# v0_3.net
KiCad netlist of a schematic drawn in EAGLE
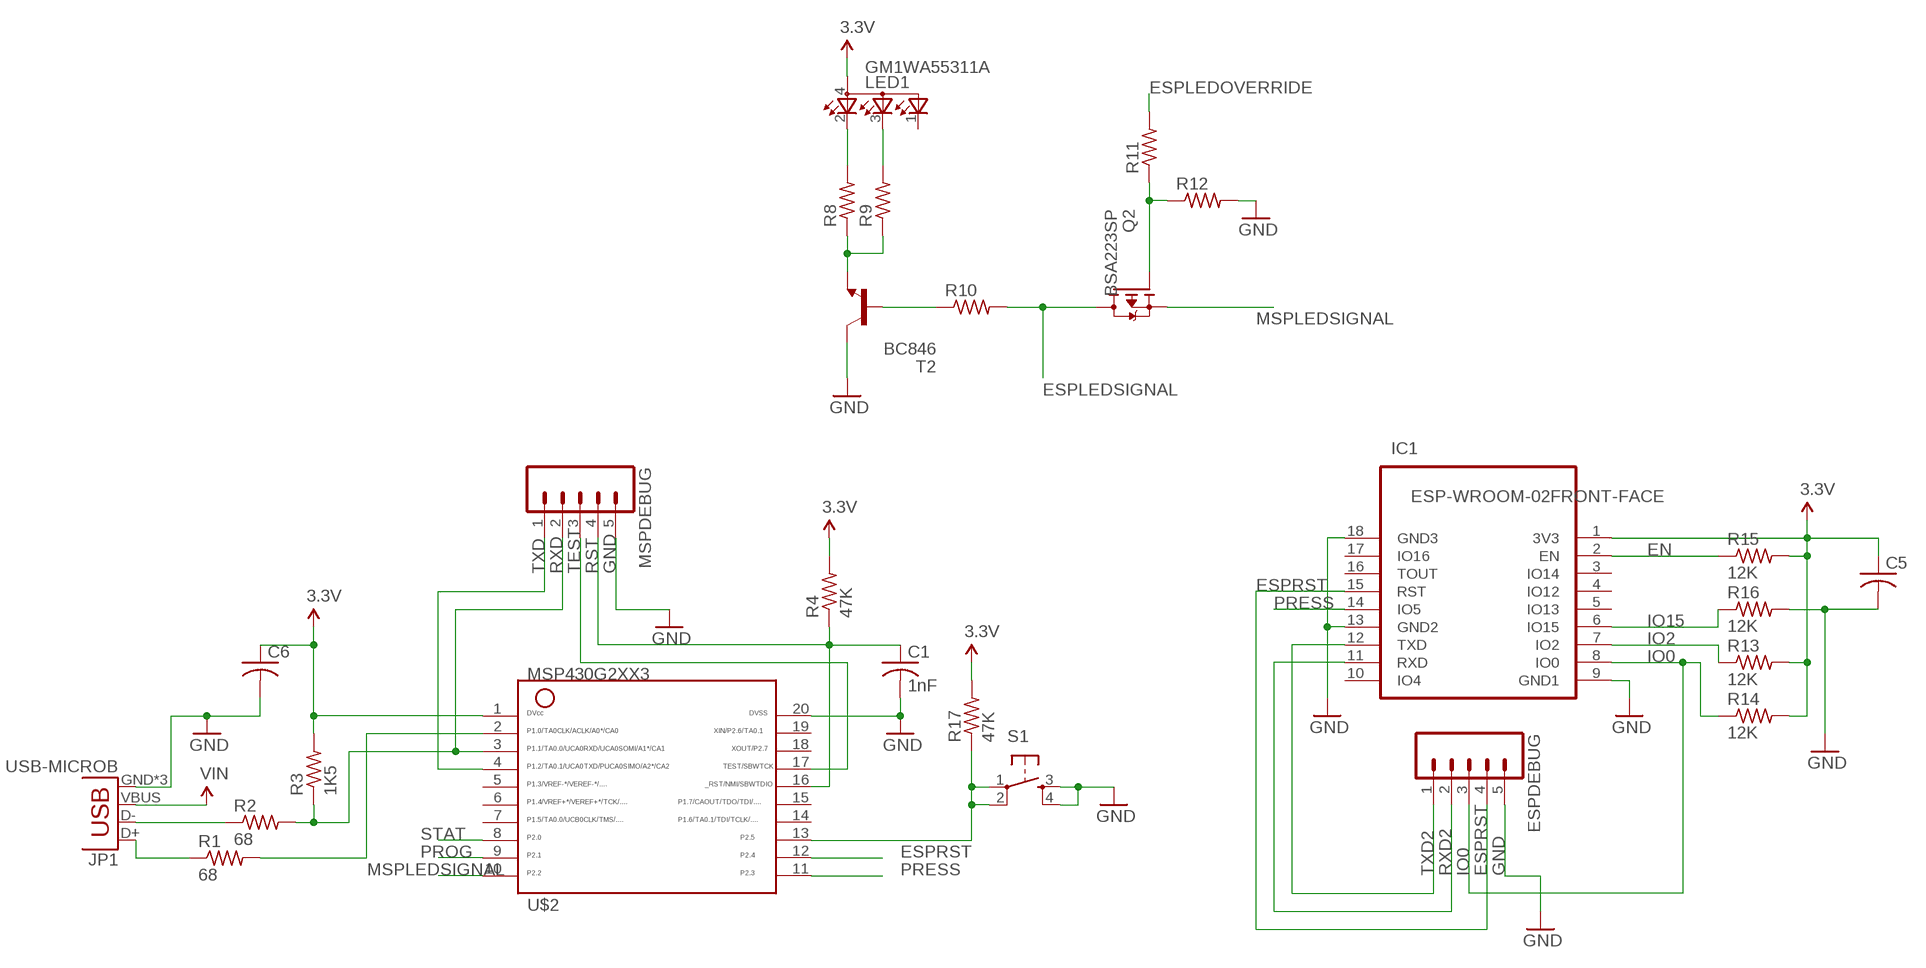
[diagram p0: schematic, sheet 1]
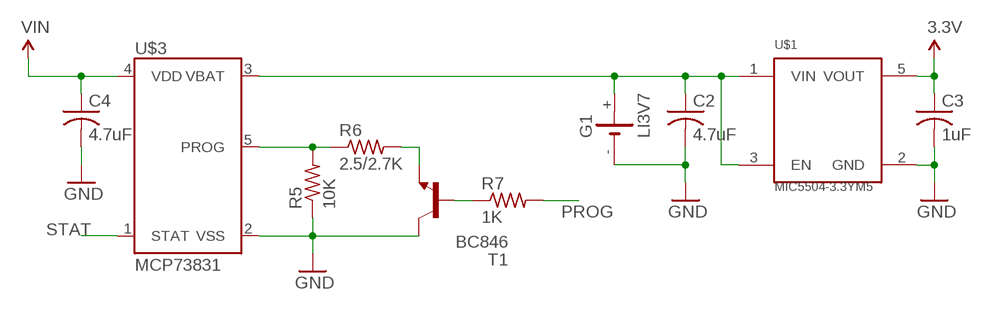
[diagram p1: schematic, sheet 2]

(export (version "E")
  (design (tool "Eeschema 10.0.6"))
  (components
    (comp (ref "C2")
      (value "4.7uF")
      (footprint "eagle-import:C0603K")
      (libsource (lib "eagle-import") (part "C-USC0603K"))
    )
    (comp (ref "C3")
      (value "1uF")
      (footprint "eagle-import:C0603K")
      (libsource (lib "eagle-import") (part "C-USC0603K"))
    )
    (comp (ref "C4")
      (value "4.7uF")
      (footprint "eagle-import:C0603K")
      (libsource (lib "eagle-import") (part "C-USC0603K"))
    )
    (comp (ref "G1")
      (value "LI3V7")
      (footprint "eagle-import:LI3V7")
      (libsource (lib "eagle-import") (part "LI3V7"))
    )
    (comp (ref "R5")
      (value "10K")
      (footprint "eagle-import:R0603")
      (libsource (lib "eagle-import") (part "R-US_R0603"))
    )
    (comp (ref "R6")
      (value "2.5/2.7K")
      (footprint "eagle-import:R0603")
      (libsource (lib "eagle-import") (part "R-US_R0603"))
    )
    (comp (ref "R7")
      (value "1K")
      (footprint "eagle-import:R0603")
      (libsource (lib "eagle-import") (part "R-US_R0603"))
    )
    (comp (ref "T1")
      (value "BC846")
      (footprint "eagle-import:SOT23")
      (libsource (lib "eagle-import") (part "BC846"))
    )
    (comp (ref "U$1")
      (value "MIC5504-3.3YM5")
      (footprint "eagle-import:SOT23-5")
      (libsource (lib "eagle-import") (part "MIC5504-3.3YM5"))
    )
    (comp (ref "U$3")
      (value "MCP73831")
      (footprint "eagle-import:SOT23-5")
      (libsource (lib "eagle-import") (part "MCP73831"))
    )
    (comp (ref "C1")
      (value "1nF")
      (footprint "eagle-import:C0603K")
      (libsource (lib "eagle-import") (part "C-USC0603K"))
    )
    (comp (ref "C5")
      (value "C-USC0603K")
      (footprint "eagle-import:C0603K")
      (libsource (lib "eagle-import") (part "C-USC0603K"))
    )
    (comp (ref "C6")
      (value "C-USC0603K")
      (footprint "eagle-import:C0603K")
      (libsource (lib "eagle-import") (part "C-USC0603K"))
    )
    (comp (ref "ESPDEBUG")
      (value "M05LOCK")
      (footprint "eagle-import:1X05_LOCK")
      (libsource (lib "eagle-import") (part "M05LOCK"))
    )
    (comp (ref "IC1")
      (value "ESP-WROOM-02FRONT-FACE")
      (footprint "eagle-import:FRONT-FACE")
      (libsource (lib "eagle-import") (part "ESP-WROOM-02FRONT-FACE"))
    )
    (comp (ref "JP1")
      (value "USB-MICROB")
      (footprint "eagle-import:USB-MICROB")
      (libsource (lib "eagle-import") (part "USB-MICROB"))
    )
    (comp (ref "LED1")
      (value "GM1WA55311A")
      (footprint "eagle-import:GM1WA55311A")
      (libsource (lib "eagle-import") (part "GM1WA55311A"))
    )
    (comp (ref "MSPDEBUG")
      (value "M05LOCK")
      (footprint "eagle-import:1X05_LOCK")
      (libsource (lib "eagle-import") (part "M05LOCK"))
    )
    (comp (ref "Q2")
      (value "BSA223SP")
      (footprint "eagle-import:SC75_INFINEON")
      (libsource (lib "eagle-import") (part "BSA223SP"))
    )
    (comp (ref "R1")
      (value "68")
      (footprint "eagle-import:R0603")
      (libsource (lib "eagle-import") (part "R-US_R0603"))
    )
    (comp (ref "R2")
      (value "68")
      (footprint "eagle-import:R0603")
      (libsource (lib "eagle-import") (part "R-US_R0603"))
    )
    (comp (ref "R3")
      (value "1K5")
      (footprint "eagle-import:R0603")
      (libsource (lib "eagle-import") (part "R-US_R0603"))
    )
    (comp (ref "R4")
      (value "47K")
      (footprint "eagle-import:R0603")
      (libsource (lib "eagle-import") (part "R-US_R0603"))
    )
    (comp (ref "R8")
      (value "R-US_R0603")
      (footprint "eagle-import:R0603")
      (libsource (lib "eagle-import") (part "R-US_R0603"))
    )
    (comp (ref "R9")
      (value "R-US_R0603")
      (footprint "eagle-import:R0603")
      (libsource (lib "eagle-import") (part "R-US_R0603"))
    )
    (comp (ref "R10")
      (value "R-US_R0603")
      (footprint "eagle-import:R0603")
      (libsource (lib "eagle-import") (part "R-US_R0603"))
    )
    (comp (ref "R11")
      (value "R-US_R0603")
      (footprint "eagle-import:R0603")
      (libsource (lib "eagle-import") (part "R-US_R0603"))
    )
    (comp (ref "R12")
      (value "R-US_R0603")
      (footprint "eagle-import:R0603")
      (libsource (lib "eagle-import") (part "R-US_R0603"))
    )
    (comp (ref "R13")
      (value "12K")
      (footprint "eagle-import:R0603")
      (libsource (lib "eagle-import") (part "R-US_R0603"))
    )
    (comp (ref "R14")
      (value "12K")
      (footprint "eagle-import:R0603")
      (libsource (lib "eagle-import") (part "R-US_R0603"))
    )
    (comp (ref "R15")
      (value "12K")
      (footprint "eagle-import:R0603")
      (libsource (lib "eagle-import") (part "R-US_R0603"))
    )
    (comp (ref "R16")
      (value "12K")
      (footprint "eagle-import:R0603")
      (libsource (lib "eagle-import") (part "R-US_R0603"))
    )
    (comp (ref "R17")
      (value "47K")
      (footprint "eagle-import:R0603")
      (libsource (lib "eagle-import") (part "R-US_R0603"))
    )
    (comp (ref "S1")
      (value "TAC_SWITCHPTH")
      (footprint "eagle-import:TACTILE-PTH")
      (libsource (lib "eagle-import") (part "TAC_SWITCHPTH"))
    )
    (comp (ref "T2")
      (value "BC846")
      (footprint "eagle-import:SOT23")
      (libsource (lib "eagle-import") (part "BC846"))
    )
    (comp (ref "U$2")
      (value "G2XX3---PW20")
      (footprint "eagle-import:PW20")
      (libsource (lib "eagle-import") (part "G2XX3---PW20"))
    )
  )
  (nets
    (net (code "1") (name "3.3V") (class "Default")
      (node (ref "C3") (pin "1") (pinfunction "1_1") (pintype "passive"))
      (node (ref "C5") (pin "1") (pinfunction "1_1") (pintype "passive"))
      (node (ref "C6") (pin "1") (pinfunction "1_1") (pintype "passive"))
      (node (ref "IC1") (pin "1") (pinfunction "3V3_1") (pintype "power_in"))
      (node (ref "LED1") (pin "4") (pinfunction "A_4") (pintype "passive"))
      (node (ref "R13") (pin "2") (pinfunction "2_2") (pintype "passive"))
      (node (ref "R14") (pin "2") (pinfunction "2_2") (pintype "passive"))
      (node (ref "R15") (pin "2") (pinfunction "2_2") (pintype "passive"))
      (node (ref "R17") (pin "2") (pinfunction "2_2") (pintype "passive"))
      (node (ref "R3") (pin "2") (pinfunction "2_2") (pintype "passive"))
      (node (ref "R4") (pin "2") (pinfunction "2_2") (pintype "passive"))
      (node (ref "U$1") (pin "5") (pinfunction "VOUT_5") (pintype "bidirectional"))
      (node (ref "U$2") (pin "1") (pinfunction "1_1") (pintype "bidirectional"))
    )
    (net (code "2") (name "EN") (class "Default")
      (node (ref "IC1") (pin "2") (pinfunction "EN_2") (pintype "bidirectional"))
      (node (ref "R15") (pin "1") (pinfunction "1_1") (pintype "passive"))
    )
    (net (code "3") (name "ESPLEDOVERRIDE") (class "Default")
      (node (ref "R11") (pin "2") (pinfunction "2_2") (pintype "passive"))
    )
    (net (code "4") (name "ESPLEDSIGNAL") (class "Default")
      (node (ref "Q2") (pin "2") (pinfunction "D_2") (pintype "passive"))
      (node (ref "R10") (pin "2") (pinfunction "2_2") (pintype "passive"))
    )
    (net (code "5") (name "ESPRST") (class "Default")
      (node (ref "ESPDEBUG") (pin "4") (pinfunction "4_4") (pintype "passive"))
      (node (ref "IC1") (pin "15") (pinfunction "RST_15") (pintype "bidirectional"))
      (node (ref "U$2") (pin "12") (pinfunction "12_12") (pintype "bidirectional"))
    )
    (net (code "6") (name "GND") (class "Default")
      (node (ref "C1") (pin "2") (pinfunction "2_2") (pintype "passive"))
      (node (ref "C2") (pin "2") (pinfunction "2_2") (pintype "passive"))
      (node (ref "C3") (pin "2") (pinfunction "2_2") (pintype "passive"))
      (node (ref "C4") (pin "2") (pinfunction "2_2") (pintype "passive"))
      (node (ref "C5") (pin "2") (pinfunction "2_2") (pintype "passive"))
      (node (ref "C6") (pin "2") (pinfunction "2_2") (pintype "passive"))
      (node (ref "ESPDEBUG") (pin "5") (pinfunction "5_5") (pintype "passive"))
      (node (ref "G1") (pin "-") (pinfunction "-_-") (pintype "passive"))
      (node (ref "IC1") (pin "13") (pinfunction "GND2_13") (pintype "power_in"))
      (node (ref "IC1") (pin "18") (pinfunction "GND3_18") (pintype "power_in"))
      (node (ref "IC1") (pin "9") (pinfunction "GND1_9") (pintype "power_in"))
      (node (ref "JP1") (pin "GND") (pinfunction "GND_GND") (pintype "bidirectional"))
      (node (ref "JP1") (pin "MT1") (pinfunction "GND_MT1") (pintype "bidirectional"))
      (node (ref "JP1") (pin "MT2") (pinfunction "GND_MT2") (pintype "bidirectional"))
      (node (ref "MSPDEBUG") (pin "5") (pinfunction "5_5") (pintype "passive"))
      (node (ref "R12") (pin "2") (pinfunction "2_2") (pintype "passive"))
      (node (ref "R16") (pin "2") (pinfunction "2_2") (pintype "passive"))
      (node (ref "R5") (pin "1") (pinfunction "1_1") (pintype "passive"))
      (node (ref "S1") (pin "3") (pinfunction "3_3") (pintype "passive"))
      (node (ref "S1") (pin "4") (pinfunction "4_4") (pintype "passive"))
      (node (ref "T1") (pin "3") (pinfunction "C_3") (pintype "passive"))
      (node (ref "T2") (pin "3") (pinfunction "C_3") (pintype "passive"))
      (node (ref "U$1") (pin "2") (pinfunction "GND_2") (pintype "bidirectional"))
      (node (ref "U$2") (pin "20") (pinfunction "20_20") (pintype "bidirectional"))
      (node (ref "U$3") (pin "2") (pinfunction "VSS_2") (pintype "power_in"))
    )
    (net (code "7") (name "IO0") (class "Default")
      (node (ref "ESPDEBUG") (pin "3") (pinfunction "3_3") (pintype "passive"))
      (node (ref "IC1") (pin "8") (pinfunction "IO0_8") (pintype "bidirectional"))
      (node (ref "R14") (pin "1") (pinfunction "1_1") (pintype "passive"))
    )
    (net (code "8") (name "IO2") (class "Default")
      (node (ref "IC1") (pin "7") (pinfunction "IO2_7") (pintype "bidirectional"))
      (node (ref "R13") (pin "1") (pinfunction "1_1") (pintype "passive"))
    )
    (net (code "9") (name "IO15") (class "Default")
      (node (ref "IC1") (pin "6") (pinfunction "IO15_6") (pintype "bidirectional"))
      (node (ref "R16") (pin "1") (pinfunction "1_1") (pintype "passive"))
    )
    (net (code "10") (name "MSPLEDSIGNAL") (class "Default")
      (node (ref "Q2") (pin "3") (pinfunction "S_3") (pintype "passive"))
      (node (ref "U$2") (pin "10") (pinfunction "10_10") (pintype "bidirectional"))
    )
    (net (code "11") (name "Net-(JP1-PadD+)") (class "Default")
      (node (ref "JP1") (pin "D+") (pinfunction "D+_D+") (pintype "bidirectional"))
      (node (ref "R1") (pin "1") (pinfunction "1_1") (pintype "passive"))
    )
    (net (code "12") (name "Net-(JP1-PadD-)") (class "Default")
      (node (ref "JP1") (pin "D-") (pinfunction "D-_D-") (pintype "bidirectional"))
      (node (ref "R2") (pin "1") (pinfunction "1_1") (pintype "passive"))
    )
    (net (code "13") (name "Net-(LED1-CBLUE)") (class "Default")
      (node (ref "LED1") (pin "3") (pinfunction "CBLUE_3") (pintype "passive"))
      (node (ref "R9") (pin "2") (pinfunction "2_2") (pintype "passive"))
    )
    (net (code "14") (name "Net-(LED1-CRED)") (class "Default")
      (node (ref "LED1") (pin "2") (pinfunction "CRED_2") (pintype "passive"))
      (node (ref "R8") (pin "2") (pinfunction "2_2") (pintype "passive"))
    )
    (net (code "15") (name "Net-(Q2-G)") (class "Default")
      (node (ref "Q2") (pin "1") (pinfunction "G_1") (pintype "passive"))
      (node (ref "R11") (pin "1") (pinfunction "1_1") (pintype "passive"))
      (node (ref "R12") (pin "1") (pinfunction "1_1") (pintype "passive"))
    )
    (net (code "16") (name "Net-(R1-Pad2)") (class "Default")
      (node (ref "R1") (pin "2") (pinfunction "2_2") (pintype "passive"))
      (node (ref "U$2") (pin "2") (pinfunction "2_2") (pintype "bidirectional"))
    )
    (net (code "17") (name "Net-(R17-Pad1)") (class "Default")
      (node (ref "R17") (pin "1") (pinfunction "1_1") (pintype "passive"))
      (node (ref "S1") (pin "1") (pinfunction "1_1") (pintype "passive"))
      (node (ref "S1") (pin "2") (pinfunction "2_2") (pintype "passive"))
      (node (ref "U$2") (pin "13") (pinfunction "13_13") (pintype "bidirectional"))
    )
    (net (code "18") (name "Net-(T1-B)") (class "Default")
      (node (ref "R7") (pin "1") (pinfunction "1_1") (pintype "passive"))
      (node (ref "T1") (pin "1") (pinfunction "B_1") (pintype "passive"))
    )
    (net (code "19") (name "Net-(T1-E)") (class "Default")
      (node (ref "R6") (pin "2") (pinfunction "2_2") (pintype "passive"))
      (node (ref "T1") (pin "2") (pinfunction "E_2") (pintype "passive"))
    )
    (net (code "20") (name "Net-(T2-B)") (class "Default")
      (node (ref "R10") (pin "1") (pinfunction "1_1") (pintype "passive"))
      (node (ref "T2") (pin "1") (pinfunction "B_1") (pintype "passive"))
    )
    (net (code "21") (name "Net-(T2-E)") (class "Default")
      (node (ref "R8") (pin "1") (pinfunction "1_1") (pintype "passive"))
      (node (ref "R9") (pin "1") (pinfunction "1_1") (pintype "passive"))
      (node (ref "T2") (pin "2") (pinfunction "E_2") (pintype "passive"))
    )
    (net (code "22") (name "Net-(U$1-EN)") (class "Default")
      (node (ref "C2") (pin "1") (pinfunction "1_1") (pintype "passive"))
      (node (ref "G1") (pin "+") (pinfunction "+_+") (pintype "passive"))
      (node (ref "U$1") (pin "1") (pinfunction "VIN_1") (pintype "bidirectional"))
      (node (ref "U$1") (pin "3") (pinfunction "EN_3") (pintype "bidirectional"))
      (node (ref "U$3") (pin "3") (pinfunction "VBAT_3") (pintype "power_in"))
    )
    (net (code "23") (name "Net-(U$3-PROG)") (class "Default")
      (node (ref "R5") (pin "2") (pinfunction "2_2") (pintype "passive"))
      (node (ref "R6") (pin "1") (pinfunction "1_1") (pintype "passive"))
      (node (ref "U$3") (pin "5") (pinfunction "PROG_5") (pintype "input"))
    )
    (net (code "24") (name "PRESS") (class "Default")
      (node (ref "IC1") (pin "14") (pinfunction "IO5_14") (pintype "open_collector"))
      (node (ref "U$2") (pin "11") (pinfunction "11_11") (pintype "bidirectional"))
    )
    (net (code "25") (name "PROG") (class "Default")
      (node (ref "R7") (pin "2") (pinfunction "2_2") (pintype "passive"))
      (node (ref "U$2") (pin "9") (pinfunction "9_9") (pintype "bidirectional"))
    )
    (net (code "26") (name "RST") (class "Default")
      (node (ref "C1") (pin "1") (pinfunction "1_1") (pintype "passive"))
      (node (ref "MSPDEBUG") (pin "4") (pinfunction "4_4") (pintype "passive"))
      (node (ref "R4") (pin "1") (pinfunction "1_1") (pintype "passive"))
      (node (ref "U$2") (pin "16") (pinfunction "16_16") (pintype "bidirectional"))
    )
    (net (code "27") (name "RXD") (class "Default")
      (node (ref "MSPDEBUG") (pin "2") (pinfunction "2_2") (pintype "passive"))
      (node (ref "R2") (pin "2") (pinfunction "2_2") (pintype "passive"))
      (node (ref "R3") (pin "1") (pinfunction "1_1") (pintype "passive"))
      (node (ref "U$2") (pin "3") (pinfunction "3_3") (pintype "bidirectional"))
    )
    (net (code "28") (name "RXD2") (class "Default")
      (node (ref "ESPDEBUG") (pin "2") (pinfunction "2_2") (pintype "passive"))
      (node (ref "IC1") (pin "11") (pinfunction "RXD_11") (pintype "bidirectional"))
    )
    (net (code "29") (name "STAT") (class "Default")
      (node (ref "U$2") (pin "8") (pinfunction "8_8") (pintype "bidirectional"))
      (node (ref "U$3") (pin "1") (pinfunction "STAT_1") (pintype "output"))
    )
    (net (code "30") (name "TEST") (class "Default")
      (node (ref "MSPDEBUG") (pin "3") (pinfunction "3_3") (pintype "passive"))
      (node (ref "U$2") (pin "17") (pinfunction "17_17") (pintype "bidirectional"))
    )
    (net (code "31") (name "TXD") (class "Default")
      (node (ref "MSPDEBUG") (pin "1") (pinfunction "1_1") (pintype "passive"))
      (node (ref "U$2") (pin "4") (pinfunction "4_4") (pintype "bidirectional"))
    )
    (net (code "32") (name "TXD2") (class "Default")
      (node (ref "ESPDEBUG") (pin "1") (pinfunction "1_1") (pintype "passive"))
      (node (ref "IC1") (pin "12") (pinfunction "TXD_12") (pintype "bidirectional"))
    )
    (net (code "33") (name "VIN") (class "Default")
      (node (ref "C4") (pin "1") (pinfunction "1_1") (pintype "passive"))
      (node (ref "JP1") (pin "VBUS") (pinfunction "VBUS_VBUS") (pintype "bidirectional"))
      (node (ref "U$3") (pin "4") (pinfunction "VDD_4") (pintype "power_in"))
    )
    (net (code "34") (name "unconnected-(IC1-IO4-Pad10)") (class "Default")
      (node (ref "IC1") (pin "10") (pinfunction "IO4_10") (pintype "bidirectional"))
    )
    (net (code "35") (name "unconnected-(IC1-IO12-Pad4)") (class "Default")
      (node (ref "IC1") (pin "4") (pinfunction "IO12_4") (pintype "bidirectional"))
    )
    (net (code "36") (name "unconnected-(IC1-IO13-Pad5)") (class "Default")
      (node (ref "IC1") (pin "5") (pinfunction "IO13_5") (pintype "bidirectional"))
    )
    (net (code "37") (name "unconnected-(IC1-IO14-Pad3)") (class "Default")
      (node (ref "IC1") (pin "3") (pinfunction "IO14_3") (pintype "bidirectional"))
    )
    (net (code "38") (name "unconnected-(IC1-IO16-Pad17)") (class "Default")
      (node (ref "IC1") (pin "17") (pinfunction "IO16_17") (pintype "bidirectional"))
    )
    (net (code "39") (name "unconnected-(IC1-TOUT-Pad16)") (class "Default")
      (node (ref "IC1") (pin "16") (pinfunction "TOUT_16") (pintype "bidirectional"))
    )
    (net (code "40") (name "unconnected-(LED1-CGREEN-Pad1)") (class "Default")
      (node (ref "LED1") (pin "1") (pinfunction "CGREEN_1") (pintype "passive"))
    )
    (net (code "41") (name "unconnected-(U$2-Pad5)") (class "Default")
      (node (ref "U$2") (pin "5") (pinfunction "5_5") (pintype "bidirectional"))
    )
    (net (code "42") (name "unconnected-(U$2-Pad6)") (class "Default")
      (node (ref "U$2") (pin "6") (pinfunction "6_6") (pintype "bidirectional"))
    )
    (net (code "43") (name "unconnected-(U$2-Pad7)") (class "Default")
      (node (ref "U$2") (pin "7") (pinfunction "7_7") (pintype "bidirectional"))
    )
    (net (code "44") (name "unconnected-(U$2-Pad14)") (class "Default")
      (node (ref "U$2") (pin "14") (pinfunction "14_14") (pintype "bidirectional"))
    )
    (net (code "45") (name "unconnected-(U$2-Pad15)") (class "Default")
      (node (ref "U$2") (pin "15") (pinfunction "15_15") (pintype "bidirectional"))
    )
    (net (code "46") (name "unconnected-(U$2-Pad18)") (class "Default")
      (node (ref "U$2") (pin "18") (pinfunction "18_18") (pintype "bidirectional"))
    )
    (net (code "47") (name "unconnected-(U$2-Pad19)") (class "Default")
      (node (ref "U$2") (pin "19") (pinfunction "19_19") (pintype "bidirectional"))
    )
  )
)
